# SDCard.net
KiCad netlist of a schematic drawn in Altium Designer
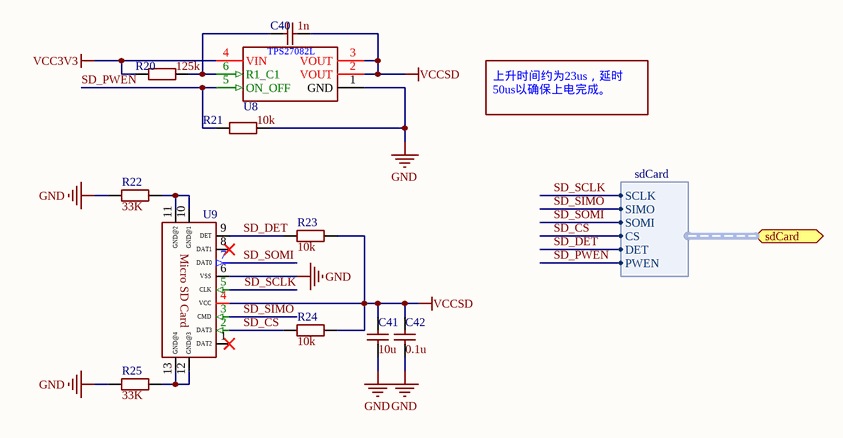
[diagram p0: SDCard.SchDoc]

(export (version "E")
  (design (tool "Eeschema 10.0.6"))
  (components
    (comp (ref "C40")
      (value "1n")
      (footprint "C0402_h")
      (description "Capacitor")
      (fields (field (name "PUBLISHER") "Altium Limited"))
      (libsource (lib "电子元件封装库") (part "贴片电容-无极性"))
    )
    (comp (ref "C41")
      (value "10u")
      (footprint "C0402_h")
      (description "Capacitor")
      (fields (field (name "PUBLISHER") "Altium Limited"))
      (libsource (lib "电子元件封装库") (part "贴片电容-无极性"))
    )
    (comp (ref "C42")
      (value "0.1u")
      (footprint "C0402_h")
      (description "Capacitor")
      (fields (field (name "PUBLISHER") "Altium Limited"))
      (libsource (lib "电子元件封装库") (part "贴片电容-无极性"))
    )
    (comp (ref "R20")
      (value "125k")
      (footprint "R0402")
      (description "Register")
      (libsource (lib "电子元件封装库") (part "贴片电阻"))
    )
    (comp (ref "R21")
      (value "10k")
      (footprint "R0402")
      (description "Register")
      (libsource (lib "") (part "贴片电阻_1"))
    )
    (comp (ref "R22")
      (value "33K")
      (footprint "R0402")
      (description "Register")
      (libsource (lib "电子元件封装库") (part "贴片电阻"))
    )
    (comp (ref "R23")
      (value "10k")
      (footprint "R0402")
      (description "Register")
      (libsource (lib "电子元件封装库") (part "贴片电阻"))
    )
    (comp (ref "R24")
      (value "10k")
      (footprint "R0402")
      (description "Register")
      (libsource (lib "电子元件封装库") (part "贴片电阻"))
    )
    (comp (ref "R25")
      (value "33K")
      (footprint "R0402")
      (description "Register")
      (libsource (lib "电子元件封装库") (part "贴片电阻"))
    )
    (comp (ref "U8")
      (value "TPS27082L")
      (footprint "SOT23-6")
      (description "load switch")
      (fields (field (name "PARTNUMBER") "TPS27082LDDC") (field (name "MANUFACTURER") "Texas Instruments"))
      (libsource (lib "电子元件封装库") (part "TPS27082LDDCR"))
    )
    (comp (ref "U9")
      (value "MicroSD")
      (footprint "MicroSD")
      (description "Micro SD Card")
      (libsource (lib "接插器件封装库") (part "Micro SD Card"))
    )
  )
  (nets
    (net (code "2") (name "/SD_CS") (class "Default")
      (node (ref "R24") (pin "1") (pinfunction "1_1") (pintype "passive"))
      (node (ref "U9") (pin "2") (pinfunction "DAT3_2") (pintype "input"))
    )
    (net (code "3") (name "/SD_DET") (class "Default")
      (node (ref "R23") (pin "1") (pinfunction "1_1") (pintype "passive"))
      (node (ref "U9") (pin "9") (pinfunction "DET_9") (pintype "passive"))
    )
    (net (code "4") (name "/SD_PWEN") (class "Default")
      (node (ref "R21") (pin "2") (pinfunction "2_2") (pintype "passive"))
      (node (ref "U8") (pin "5") (pinfunction "ON_OFF_5") (pintype "input"))
    )
    (net (code "5") (name "/SD_SCLK") (class "Default")
      (node (ref "U9") (pin "5") (pinfunction "CLK_5") (pintype "input"))
    )
    (net (code "6") (name "/SD_SIMO") (class "Default")
      (node (ref "U9") (pin "3") (pinfunction "CMD_3") (pintype "input"))
    )
    (net (code "7") (name "/SD_SOMI") (class "Default")
      (node (ref "U9") (pin "7") (pinfunction "DAT0_7") (pintype "output"))
    )
    (net (code "9") (name "GND") (class "Default")
      (node (ref "C41") (pin "1") (pinfunction "1_1") (pintype "passive"))
      (node (ref "C42") (pin "1") (pinfunction "1_1") (pintype "passive"))
      (node (ref "R21") (pin "1") (pinfunction "1_1") (pintype "passive"))
      (node (ref "R22") (pin "1") (pinfunction "1_1") (pintype "passive"))
      (node (ref "R25") (pin "1") (pinfunction "1_1") (pintype "passive"))
      (node (ref "U8") (pin "1") (pinfunction "GND_1") (pintype "power_in"))
      (node (ref "U9") (pin "6") (pinfunction "VSS_6") (pintype "power_in"))
    )
    (net (code "10") (name "Net-(U8-R1_C1)") (class "Default")
      (node (ref "C40") (pin "1") (pinfunction "1_1") (pintype "passive"))
      (node (ref "R20") (pin "2") (pinfunction "2_2") (pintype "passive"))
      (node (ref "U8") (pin "6") (pinfunction "R1_C1_6") (pintype "input"))
    )
    (net (code "11") (name "Net-(U9-GND@1)") (class "Default")
      (node (ref "R22") (pin "2") (pinfunction "2_2") (pintype "passive"))
      (node (ref "U9") (pin "10") (pinfunction "GND@1_10") (pintype "passive"))
      (node (ref "U9") (pin "11") (pinfunction "GND@2_11") (pintype "passive"))
    )
    (net (code "12") (name "Net-(U9-GND@3)") (class "Default")
      (node (ref "R25") (pin "2") (pinfunction "2_2") (pintype "passive"))
      (node (ref "U9") (pin "12") (pinfunction "GND@3_12") (pintype "passive"))
      (node (ref "U9") (pin "13") (pinfunction "GND@4_13") (pintype "passive"))
    )
    (net (code "13") (name "VCC3V3") (class "Default")
      (node (ref "R20") (pin "1") (pinfunction "1_1") (pintype "passive"))
      (node (ref "U8") (pin "4") (pinfunction "VIN_4") (pintype "power_in"))
    )
    (net (code "14") (name "VCCSD") (class "Default")
      (node (ref "C40") (pin "2") (pinfunction "2_2") (pintype "passive"))
      (node (ref "C41") (pin "2") (pinfunction "2_2") (pintype "passive"))
      (node (ref "C42") (pin "2") (pinfunction "2_2") (pintype "passive"))
      (node (ref "R23") (pin "2") (pinfunction "2_2") (pintype "passive"))
      (node (ref "R24") (pin "2") (pinfunction "2_2") (pintype "passive"))
      (node (ref "U8") (pin "2") (pinfunction "VOUT_2") (pintype "power_in"))
      (node (ref "U8") (pin "3") (pinfunction "VOUT_3") (pintype "power_in"))
      (node (ref "U9") (pin "4") (pinfunction "VCC_4") (pintype "passive"))
    )
    (net (code "15") (name "unconnected-(U9-DAT1-Pad8)") (class "Default")
      (node (ref "U9") (pin "8") (pinfunction "DAT1_8") (pintype "power_in+no_connect"))
    )
    (net (code "16") (name "unconnected-(U9-DAT2-Pad1)") (class "Default")
      (node (ref "U9") (pin "1") (pinfunction "DAT2_1") (pintype "passive+no_connect"))
    )
  )
)
